# SCH_USB.net
KiCad netlist of a schematic drawn in Altium Designer
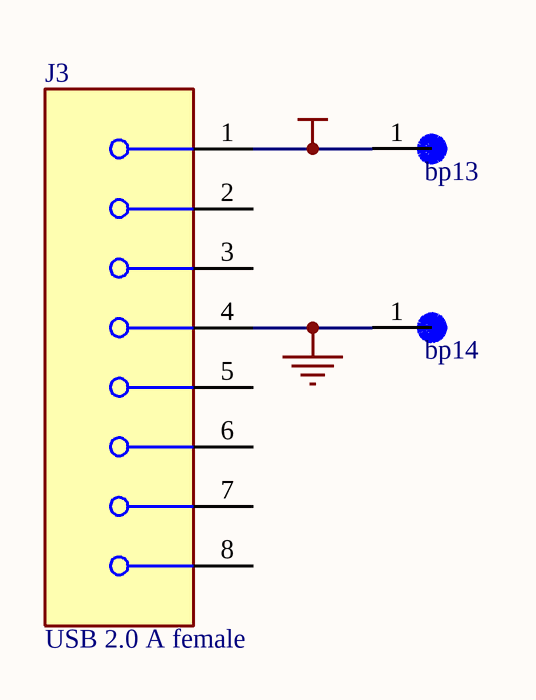
[diagram p0: SCH_USB.SchDoc]

(export (version "E")
  (design (tool "Eeschema 10.0.6"))
  (components
    (comp (ref "bp13")
      (value "Battery Pad")
      (footprint "Battery pad")
      (libsource (lib "Schlib1") (part "Battery Pad"))
    )
    (comp (ref "bp14")
      (value "Battery Pad")
      (footprint "Battery pad")
      (libsource (lib "Schlib1") (part "Battery Pad"))
    )
    (comp (ref "J3")
      (value "USB 2.0 A female")
      (footprint "usbA2F_Molex_67329-8000_0")
      (libsource (lib "Schlib1") (part "67329-8000"))
    )
  )
  (nets
    (net (code "1") (name "+5") (class "Default")
      (node (ref "J3") (pin "1") (pinfunction "1_1") (pintype "passive"))
      (node (ref "bp13") (pin "1") (pinfunction "1_1") (pintype "passive"))
    )
    (net (code "2") (name "GND") (class "Default")
      (node (ref "J3") (pin "4") (pinfunction "4_4") (pintype "passive"))
      (node (ref "bp14") (pin "1") (pinfunction "1_1") (pintype "passive"))
    )
    (net (code "3") (name "unconnected-(J3-MNT_1-Pad5)") (class "Default")
      (node (ref "J3") (pin "5") (pinfunction "MNT_1_5") (pintype "passive"))
    )
    (net (code "4") (name "unconnected-(J3-MNT_2-Pad6)") (class "Default")
      (node (ref "J3") (pin "6") (pinfunction "MNT_2_6") (pintype "passive"))
    )
    (net (code "5") (name "unconnected-(J3-MNT_3-Pad7)") (class "Default")
      (node (ref "J3") (pin "7") (pinfunction "MNT_3_7") (pintype "passive"))
    )
    (net (code "6") (name "unconnected-(J3-MNT_4-Pad8)") (class "Default")
      (node (ref "J3") (pin "8") (pinfunction "MNT_4_8") (pintype "passive"))
    )
    (net (code "7") (name "unconnected-(J3-Pad2)") (class "Default")
      (node (ref "J3") (pin "2") (pinfunction "2_2") (pintype "passive"))
    )
    (net (code "8") (name "unconnected-(J3-Pad3)") (class "Default")
      (node (ref "J3") (pin "3") (pinfunction "3_3") (pintype "passive"))
    )
  )
)
